# bipap_mechanical_tester.net
KiCad netlist of a schematic drawn in EAGLE
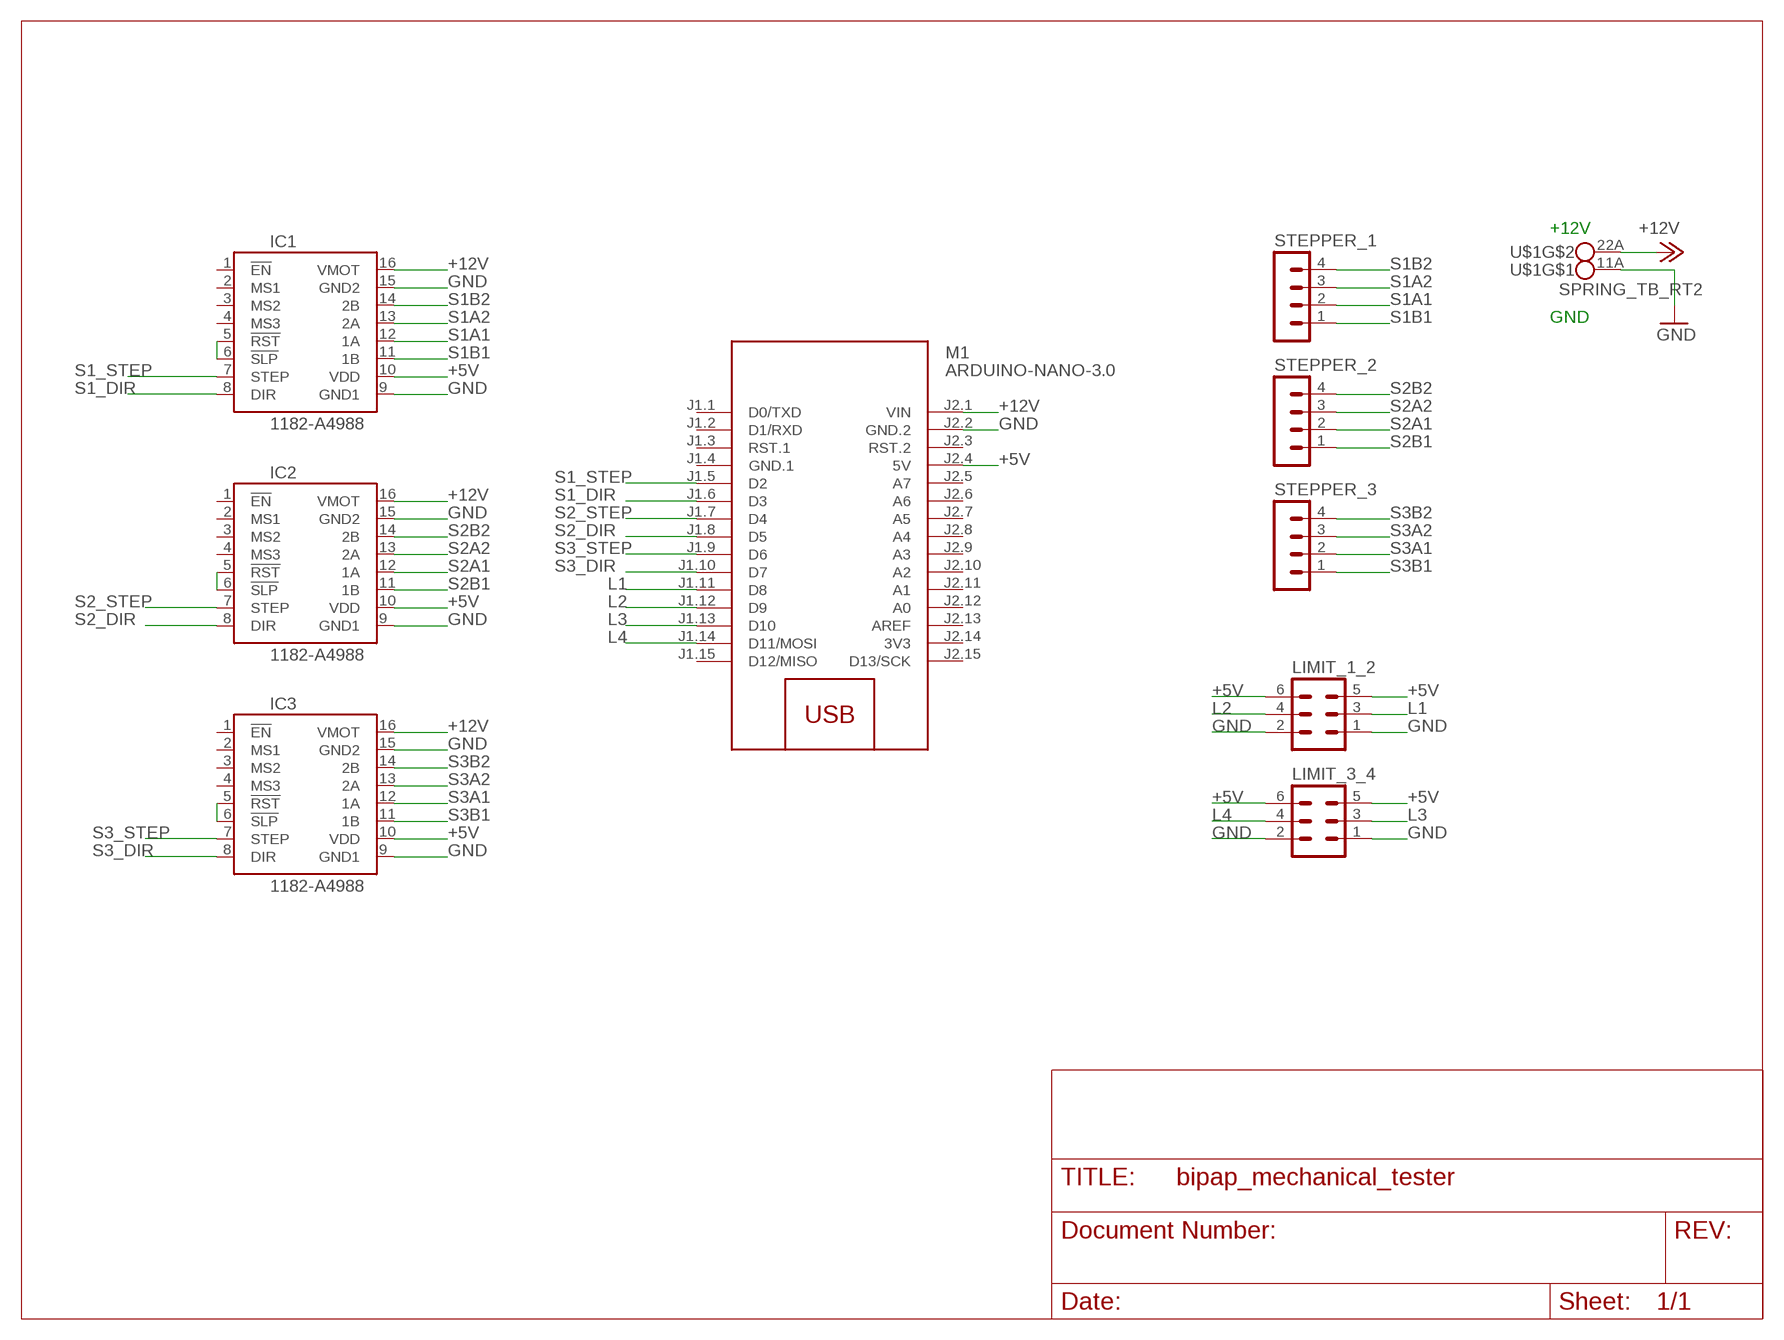
[diagram p0: schematic, sheet 1]

(export (version "E")
  (design (tool "Eeschema 10.0.6"))
  (components
    (comp (ref "IC1")
      (value "1182-A4988")
      (footprint "eagle-import:A4988")
      (libsource (lib "eagle-import") (part "1182-A4988"))
    )
    (comp (ref "IC2")
      (value "1182-A4988")
      (footprint "eagle-import:A4988")
      (libsource (lib "eagle-import") (part "1182-A4988"))
    )
    (comp (ref "IC3")
      (value "1182-A4988")
      (footprint "eagle-import:A4988")
      (libsource (lib "eagle-import") (part "1182-A4988"))
    )
    (comp (ref "LIMIT_1_2")
      (value "MA03-2")
      (footprint "eagle-import:MA03-2")
      (libsource (lib "eagle-import") (part "MA03-2"))
    )
    (comp (ref "LIMIT_3_4")
      (value "MA03-2")
      (footprint "eagle-import:MA03-2")
      (libsource (lib "eagle-import") (part "MA03-2"))
    )
    (comp (ref "M1")
      (value "ARDUINO-NANO-3.0")
      (footprint "eagle-import:ARDUINO-NANO-3.0")
      (libsource (lib "eagle-import") (part "ARDUINO-NANO-3.0"))
    )
    (comp (ref "STEPPER_1")
      (value "MA04-1")
      (footprint "eagle-import:MA04-1")
      (libsource (lib "eagle-import") (part "MA04-1"))
    )
    (comp (ref "STEPPER_2")
      (value "MA04-1")
      (footprint "eagle-import:MA04-1")
      (libsource (lib "eagle-import") (part "MA04-1"))
    )
    (comp (ref "STEPPER_3")
      (value "MA04-1")
      (footprint "eagle-import:MA04-1")
      (libsource (lib "eagle-import") (part "MA04-1"))
    )
    (comp (ref "U$1")
      (value "SPRING_TB_RT2")
      (footprint "eagle-import:SPRING_TB_RT2")
      (libsource (lib "eagle-import") (part "SPRING_TB_RT2"))
    )
  )
  (nets
    (net (code "1") (name "+12V") (class "Default")
      (node (ref "IC1") (pin "16") (pinfunction "VMOT_16") (pintype "power_in"))
      (node (ref "IC2") (pin "16") (pinfunction "VMOT_16") (pintype "power_in"))
      (node (ref "IC3") (pin "16") (pinfunction "VMOT_16") (pintype "power_in"))
      (node (ref "M1") (pin "J2.1") (pinfunction "VIN_J2.1") (pintype "power_in"))
      (node (ref "U$1") (pin "2A") (pinfunction "2_2A") (pintype "passive"))
    )
    (net (code "2") (name "/+5V") (class "Default")
      (node (ref "IC1") (pin "10") (pinfunction "VDD_10") (pintype "power_in"))
      (node (ref "IC2") (pin "10") (pinfunction "VDD_10") (pintype "power_in"))
      (node (ref "IC3") (pin "10") (pinfunction "VDD_10") (pintype "power_in"))
      (node (ref "LIMIT_1_2") (pin "5") (pinfunction "5_5") (pintype "passive"))
      (node (ref "LIMIT_1_2") (pin "6") (pinfunction "6_6") (pintype "passive"))
      (node (ref "LIMIT_3_4") (pin "5") (pinfunction "5_5") (pintype "passive"))
      (node (ref "LIMIT_3_4") (pin "6") (pinfunction "6_6") (pintype "passive"))
      (node (ref "M1") (pin "J2.4") (pinfunction "5V_J2.4") (pintype "power_in"))
    )
    (net (code "3") (name "/3V3") (class "Default")
      (node (ref "M1") (pin "J2.14") (pinfunction "3V3_J2.14") (pintype "power_in"))
    )
    (net (code "4") (name "/GND.1") (class "Default")
      (node (ref "M1") (pin "J1.4") (pinfunction "GND.1_J1.4") (pintype "power_in"))
    )
    (net (code "5") (name "/L1") (class "Default")
      (node (ref "LIMIT_1_2") (pin "3") (pinfunction "3_3") (pintype "passive"))
      (node (ref "M1") (pin "J1.11") (pinfunction "D8_J1.11") (pintype "bidirectional"))
    )
    (net (code "6") (name "/L2") (class "Default")
      (node (ref "LIMIT_1_2") (pin "4") (pinfunction "4_4") (pintype "passive"))
      (node (ref "M1") (pin "J1.12") (pinfunction "D9_J1.12") (pintype "bidirectional"))
    )
    (net (code "7") (name "/L3") (class "Default")
      (node (ref "LIMIT_3_4") (pin "3") (pinfunction "3_3") (pintype "passive"))
      (node (ref "M1") (pin "J1.13") (pinfunction "D10_J1.13") (pintype "bidirectional"))
    )
    (net (code "8") (name "/L4") (class "Default")
      (node (ref "LIMIT_3_4") (pin "4") (pinfunction "4_4") (pintype "passive"))
      (node (ref "M1") (pin "J1.14") (pinfunction "D11/MOSI_J1.14") (pintype "bidirectional"))
    )
    (net (code "9") (name "/S1A1") (class "Default")
      (node (ref "IC1") (pin "12") (pinfunction "1A_12") (pintype "output"))
      (node (ref "STEPPER_1") (pin "2") (pinfunction "2_2") (pintype "passive"))
    )
    (net (code "10") (name "/S1A2") (class "Default")
      (node (ref "IC1") (pin "13") (pinfunction "2A_13") (pintype "output"))
      (node (ref "STEPPER_1") (pin "3") (pinfunction "3_3") (pintype "passive"))
    )
    (net (code "11") (name "/S1B1") (class "Default")
      (node (ref "IC1") (pin "11") (pinfunction "1B_11") (pintype "output"))
      (node (ref "STEPPER_1") (pin "1") (pinfunction "1_1") (pintype "passive"))
    )
    (net (code "12") (name "/S1B2") (class "Default")
      (node (ref "IC1") (pin "14") (pinfunction "2B_14") (pintype "output"))
      (node (ref "STEPPER_1") (pin "4") (pinfunction "4_4") (pintype "passive"))
    )
    (net (code "13") (name "/S1_DIR") (class "Default")
      (node (ref "IC1") (pin "8") (pinfunction "DIR_8") (pintype "input"))
      (node (ref "M1") (pin "J1.6") (pinfunction "D3_J1.6") (pintype "bidirectional"))
    )
    (net (code "14") (name "/S1_STEP") (class "Default")
      (node (ref "IC1") (pin "7") (pinfunction "STEP_7") (pintype "input"))
      (node (ref "M1") (pin "J1.5") (pinfunction "D2_J1.5") (pintype "bidirectional"))
    )
    (net (code "15") (name "/S2A1") (class "Default")
      (node (ref "IC2") (pin "12") (pinfunction "1A_12") (pintype "output"))
      (node (ref "STEPPER_2") (pin "2") (pinfunction "2_2") (pintype "passive"))
    )
    (net (code "16") (name "/S2A2") (class "Default")
      (node (ref "IC2") (pin "13") (pinfunction "2A_13") (pintype "output"))
      (node (ref "STEPPER_2") (pin "3") (pinfunction "3_3") (pintype "passive"))
    )
    (net (code "17") (name "/S2B1") (class "Default")
      (node (ref "IC2") (pin "11") (pinfunction "1B_11") (pintype "output"))
      (node (ref "STEPPER_2") (pin "1") (pinfunction "1_1") (pintype "passive"))
    )
    (net (code "18") (name "/S2B2") (class "Default")
      (node (ref "IC2") (pin "14") (pinfunction "2B_14") (pintype "output"))
      (node (ref "STEPPER_2") (pin "4") (pinfunction "4_4") (pintype "passive"))
    )
    (net (code "19") (name "/S2_DIR") (class "Default")
      (node (ref "IC2") (pin "8") (pinfunction "DIR_8") (pintype "input"))
      (node (ref "M1") (pin "J1.8") (pinfunction "D5_J1.8") (pintype "bidirectional"))
    )
    (net (code "20") (name "/S2_STEP") (class "Default")
      (node (ref "IC2") (pin "7") (pinfunction "STEP_7") (pintype "input"))
      (node (ref "M1") (pin "J1.7") (pinfunction "D4_J1.7") (pintype "bidirectional"))
    )
    (net (code "21") (name "/S3A1") (class "Default")
      (node (ref "IC3") (pin "12") (pinfunction "1A_12") (pintype "output"))
      (node (ref "STEPPER_3") (pin "2") (pinfunction "2_2") (pintype "passive"))
    )
    (net (code "22") (name "/S3A2") (class "Default")
      (node (ref "IC3") (pin "13") (pinfunction "2A_13") (pintype "output"))
      (node (ref "STEPPER_3") (pin "3") (pinfunction "3_3") (pintype "passive"))
    )
    (net (code "23") (name "/S3B1") (class "Default")
      (node (ref "IC3") (pin "11") (pinfunction "1B_11") (pintype "output"))
      (node (ref "STEPPER_3") (pin "1") (pinfunction "1_1") (pintype "passive"))
    )
    (net (code "24") (name "/S3B2") (class "Default")
      (node (ref "IC3") (pin "14") (pinfunction "2B_14") (pintype "output"))
      (node (ref "STEPPER_3") (pin "4") (pinfunction "4_4") (pintype "passive"))
    )
    (net (code "25") (name "/S3_DIR") (class "Default")
      (node (ref "IC3") (pin "8") (pinfunction "DIR_8") (pintype "input"))
      (node (ref "M1") (pin "J1.10") (pinfunction "D7_J1.10") (pintype "bidirectional"))
    )
    (net (code "26") (name "/S3_STEP") (class "Default")
      (node (ref "IC3") (pin "7") (pinfunction "STEP_7") (pintype "input"))
      (node (ref "M1") (pin "J1.9") (pinfunction "D6_J1.9") (pintype "bidirectional"))
    )
    (net (code "27") (name "GND") (class "Default")
      (node (ref "IC1") (pin "15") (pinfunction "GND2_15") (pintype "power_in"))
      (node (ref "IC1") (pin "9") (pinfunction "GND1_9") (pintype "power_in"))
      (node (ref "IC2") (pin "15") (pinfunction "GND2_15") (pintype "power_in"))
      (node (ref "IC2") (pin "9") (pinfunction "GND1_9") (pintype "power_in"))
      (node (ref "IC3") (pin "15") (pinfunction "GND2_15") (pintype "power_in"))
      (node (ref "IC3") (pin "9") (pinfunction "GND1_9") (pintype "power_in"))
      (node (ref "LIMIT_1_2") (pin "1") (pinfunction "1_1") (pintype "passive"))
      (node (ref "LIMIT_1_2") (pin "2") (pinfunction "2_2") (pintype "passive"))
      (node (ref "LIMIT_3_4") (pin "1") (pinfunction "1_1") (pintype "passive"))
      (node (ref "LIMIT_3_4") (pin "2") (pinfunction "2_2") (pintype "passive"))
      (node (ref "M1") (pin "J2.2") (pinfunction "GND.2_J2.2") (pintype "power_in"))
      (node (ref "U$1") (pin "1A") (pinfunction "2_1A") (pintype "passive"))
    )
    (net (code "28") (name "Net-(IC1-~{RST})") (class "Default")
      (node (ref "IC1") (pin "5") (pinfunction "~{RST}_5") (pintype "passive"))
      (node (ref "IC1") (pin "6") (pinfunction "~{SLP}_6") (pintype "passive"))
    )
    (net (code "29") (name "Net-(IC2-~{RST})") (class "Default")
      (node (ref "IC2") (pin "5") (pinfunction "~{RST}_5") (pintype "passive"))
      (node (ref "IC2") (pin "6") (pinfunction "~{SLP}_6") (pintype "passive"))
    )
    (net (code "30") (name "Net-(IC3-~{RST})") (class "Default")
      (node (ref "IC3") (pin "5") (pinfunction "~{RST}_5") (pintype "passive"))
      (node (ref "IC3") (pin "6") (pinfunction "~{SLP}_6") (pintype "passive"))
    )
    (net (code "31") (name "unconnected-(IC1-MS1-Pad2)") (class "Default")
      (node (ref "IC1") (pin "2") (pinfunction "MS1_2") (pintype "passive"))
    )
    (net (code "32") (name "unconnected-(IC1-MS2-Pad3)") (class "Default")
      (node (ref "IC1") (pin "3") (pinfunction "MS2_3") (pintype "passive"))
    )
    (net (code "33") (name "unconnected-(IC1-MS3-Pad4)") (class "Default")
      (node (ref "IC1") (pin "4") (pinfunction "MS3_4") (pintype "passive"))
    )
    (net (code "34") (name "unconnected-(IC1-~{EN}-Pad1)") (class "Default")
      (node (ref "IC1") (pin "1") (pinfunction "~{EN}_1") (pintype "passive"))
    )
    (net (code "35") (name "unconnected-(IC2-MS1-Pad2)") (class "Default")
      (node (ref "IC2") (pin "2") (pinfunction "MS1_2") (pintype "passive"))
    )
    (net (code "36") (name "unconnected-(IC2-MS2-Pad3)") (class "Default")
      (node (ref "IC2") (pin "3") (pinfunction "MS2_3") (pintype "passive"))
    )
    (net (code "37") (name "unconnected-(IC2-MS3-Pad4)") (class "Default")
      (node (ref "IC2") (pin "4") (pinfunction "MS3_4") (pintype "passive"))
    )
    (net (code "38") (name "unconnected-(IC2-~{EN}-Pad1)") (class "Default")
      (node (ref "IC2") (pin "1") (pinfunction "~{EN}_1") (pintype "passive"))
    )
    (net (code "39") (name "unconnected-(IC3-MS1-Pad2)") (class "Default")
      (node (ref "IC3") (pin "2") (pinfunction "MS1_2") (pintype "passive"))
    )
    (net (code "40") (name "unconnected-(IC3-MS2-Pad3)") (class "Default")
      (node (ref "IC3") (pin "3") (pinfunction "MS2_3") (pintype "passive"))
    )
    (net (code "41") (name "unconnected-(IC3-MS3-Pad4)") (class "Default")
      (node (ref "IC3") (pin "4") (pinfunction "MS3_4") (pintype "passive"))
    )
    (net (code "42") (name "unconnected-(IC3-~{EN}-Pad1)") (class "Default")
      (node (ref "IC3") (pin "1") (pinfunction "~{EN}_1") (pintype "passive"))
    )
    (net (code "43") (name "unconnected-(M1-A0-PadJ2.12)") (class "Default")
      (node (ref "M1") (pin "J2.12") (pinfunction "A0_J2.12") (pintype "bidirectional"))
    )
    (net (code "44") (name "unconnected-(M1-A1-PadJ2.11)") (class "Default")
      (node (ref "M1") (pin "J2.11") (pinfunction "A1_J2.11") (pintype "bidirectional"))
    )
    (net (code "45") (name "unconnected-(M1-A2-PadJ2.10)") (class "Default")
      (node (ref "M1") (pin "J2.10") (pinfunction "A2_J2.10") (pintype "bidirectional"))
    )
    (net (code "46") (name "unconnected-(M1-A3-PadJ2.9)") (class "Default")
      (node (ref "M1") (pin "J2.9") (pinfunction "A3_J2.9") (pintype "bidirectional"))
    )
    (net (code "47") (name "unconnected-(M1-A4-PadJ2.8)") (class "Default")
      (node (ref "M1") (pin "J2.8") (pinfunction "A4_J2.8") (pintype "bidirectional"))
    )
    (net (code "48") (name "unconnected-(M1-A5-PadJ2.7)") (class "Default")
      (node (ref "M1") (pin "J2.7") (pinfunction "A5_J2.7") (pintype "bidirectional"))
    )
    (net (code "49") (name "unconnected-(M1-A6-PadJ2.6)") (class "Default")
      (node (ref "M1") (pin "J2.6") (pinfunction "A6_J2.6") (pintype "bidirectional"))
    )
    (net (code "50") (name "unconnected-(M1-A7-PadJ2.5)") (class "Default")
      (node (ref "M1") (pin "J2.5") (pinfunction "A7_J2.5") (pintype "bidirectional"))
    )
    (net (code "51") (name "unconnected-(M1-AREF-PadJ2.13)") (class "Default")
      (node (ref "M1") (pin "J2.13") (pinfunction "AREF_J2.13") (pintype "bidirectional"))
    )
    (net (code "52") (name "unconnected-(M1-D0{slash}TXD-PadJ1.1)") (class "Default")
      (node (ref "M1") (pin "J1.1") (pinfunction "D0/TXD_J1.1") (pintype "bidirectional"))
    )
    (net (code "53") (name "unconnected-(M1-D1{slash}RXD-PadJ1.2)") (class "Default")
      (node (ref "M1") (pin "J1.2") (pinfunction "D1/RXD_J1.2") (pintype "bidirectional"))
    )
    (net (code "54") (name "unconnected-(M1-D12{slash}MISO-PadJ1.15)") (class "Default")
      (node (ref "M1") (pin "J1.15") (pinfunction "D12/MISO_J1.15") (pintype "bidirectional"))
    )
    (net (code "55") (name "unconnected-(M1-D13{slash}SCK-PadJ2.15)") (class "Default")
      (node (ref "M1") (pin "J2.15") (pinfunction "D13/SCK_J2.15") (pintype "bidirectional"))
    )
    (net (code "56") (name "unconnected-(M1-RST.1-PadJ1.3)") (class "Default")
      (node (ref "M1") (pin "J1.3") (pinfunction "RST.1_J1.3") (pintype "bidirectional"))
    )
    (net (code "57") (name "unconnected-(M1-RST.2-PadJ2.3)") (class "Default")
      (node (ref "M1") (pin "J2.3") (pinfunction "RST.2_J2.3") (pintype "bidirectional"))
    )
    (net (code "58") (name "unconnected-(U$1-Pad1)") (class "Default")
      (node (ref "U$1") (pin "1") (pinfunction "1_1") (pintype "passive"))
    )
    (net (code "59") (name "unconnected-(U$1B-1-Pad2)") (class "Default")
      (node (ref "U$1") (pin "2") (pinfunction "1_2") (pintype "passive"))
    )
  )
)
